# Sheet_1.net
KiCad netlist of a schematic drawn in Altium Designer
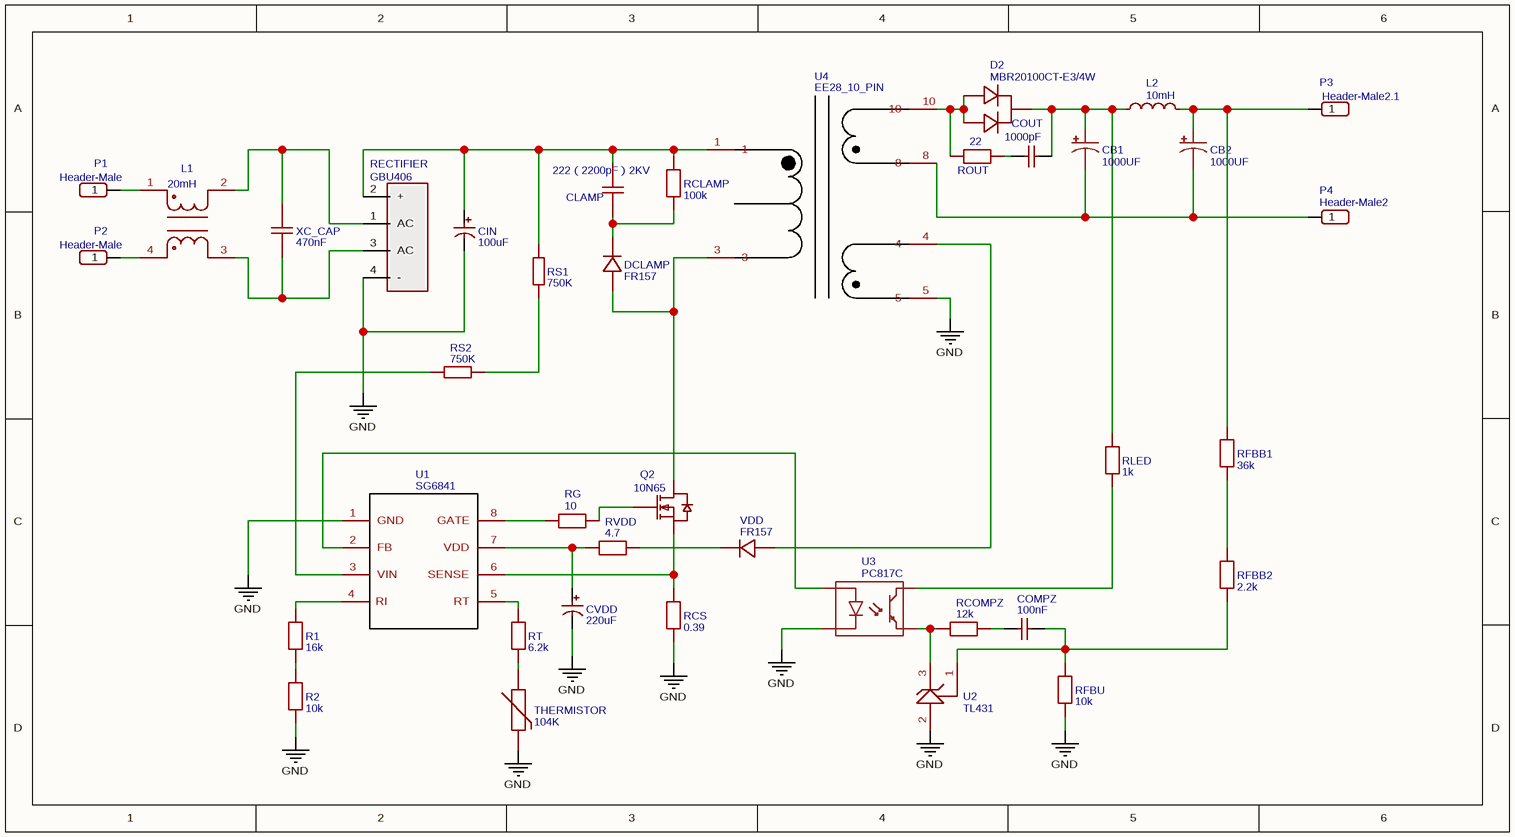
[diagram p0: Sheet_1.schdoc]

(export (version "E")
  (design (tool "Eeschema 10.0.6"))
  (components
    (comp (ref "CB1")
      (value "1000UF")
      (description "CAP-08070")
      (fields (field (name "CONTRIBUTOR") "SparkFun"))
      (libsource (lib "altium-import") (part "root_0_1000UF_"))
    )
    (comp (ref "CB2")
      (value "1000UF")
      (description "CAP-08070")
      (fields (field (name "CONTRIBUTOR") "SparkFun"))
      (libsource (lib "altium-import") (part "root_0_1000UF_"))
    )
    (comp (ref "CIN")
      (value "100uF")
      (fields
        (field (name "BOM_MANUFACTURER PART") "400V 100uF 18X30")
        (field (name "BOM_SUPPLIER PART") "C2767")
      )
      (libsource (lib "altium-import") (part "root_3_100uF_"))
    )
    (comp (ref "CLAMP")
      (value "222（2200pF）2KV")
      (fields (field (name "BOM_SUPPLIER PART") "C24926"))
      (libsource (lib "altium-import") (part "root_1_222（2200pF）2KV_"))
    )
    (comp (ref "COMPZ")
      (value "100nF")
      (fields
        (field (name "BOM_MANUFACTURER PART") "104/100V 20%")
        (field (name "BOM_SUPPLIER PART") "C26856")
      )
      (libsource (lib "altium-import") (part "root_0_100nF_"))
    )
    (comp (ref "COUT")
      (value "1000pF")
      (fields
        (field (name "BOM_MANUFACTURER PART") "102M 400V Y5V")
        (field (name "BOM_SUPPLIER PART") "C3704")
      )
      (libsource (lib "altium-import") (part "root_0_1000pF_"))
    )
    (comp (ref "CVDD")
      (value "220uF")
      (fields (field (name "BOM_MANUFACTURER PART") "220uf/35V") (field (name "BOM_SUPPLIER PART") "C2063"))
      (libsource (lib "altium-import") (part "root_3_220uF_"))
    )
    (comp (ref "D2")
      (value "MBR20100CT-E3/4W")
      (fields (field (name "BOM_SUPPLIER PART") "C222466") (field (name "CONTRIBUTOR") "LCSC"))
      (libsource (lib "altium-import") (part "root_3_MBR20100CT-E3/4W_"))
    )
    (comp (ref "DCLAMP")
      (value "FR157")
      (fields (field (name "BOM_SUPPLIER PART") "C2467"))
      (libsource (lib "altium-import") (part "root_1_FR157_"))
    )
    (comp (ref "L1")
      (value "20mH")
      (fields
        (field (name "BOM_SUPPLIER PART") "C148474")
        (field (name "BOM_MANUFACTURER PART") "UU9.8-10mH")
        (field (name "CONTRIBUTOR") "LCSC")
      )
      (libsource (lib "altium-import") (part "root_0_20mH_"))
    )
    (comp (ref "L2")
      (value "10mH")
      (fields
        (field (name "BOM_MANUFACTURER PART") "VLU0608-103K")
        (field (name "BOM_SUPPLIER PART") "C72613")
      )
      (libsource (lib "altium-import") (part "root_0_10mH_"))
    )
    (comp (ref "P1")
      (value "Header-Male")
      (fields
        (field (name "BOM_MANUFACTURER PART") "Header-Male-2.54_1x1")
        (field (name "BOM_SUPPLIER PART") "C81276")
      )
      (libsource (lib "altium-import") (part "root_2_Header-Male_"))
    )
    (comp (ref "P2")
      (value "Header-Male")
      (fields
        (field (name "BOM_MANUFACTURER PART") "Header-Male-2.54_1x1")
        (field (name "BOM_SUPPLIER PART") "C81276")
      )
      (libsource (lib "altium-import") (part "root_2_Header-Male_"))
    )
    (comp (ref "P3")
      (value "Header-Male2.1")
      (fields
        (field (name "BOM_MANUFACTURER PART") "Header-Male-2.54_1x1")
        (field (name "BOM_SUPPLIER PART") "C81276")
      )
      (libsource (lib "altium-import") (part "root_0_Header-Male2.1_"))
    )
    (comp (ref "P4")
      (value "Header-Male2")
      (fields
        (field (name "BOM_MANUFACTURER PART") "Header-Male-2.54_1x1")
        (field (name "BOM_SUPPLIER PART") "C81276")
      )
      (libsource (lib "altium-import") (part "root_0_Header-Male2_"))
    )
    (comp (ref "Q2")
      (value "10N65")
      (fields
        (field (name "BOM_MANUFACTURER PART") "10N65KL-TF3-T")
        (field (name "BOM_SUPPLIER PART") "C74166")
      )
      (libsource (lib "altium-import") (part "root_0_10N65_"))
    )
    (comp (ref "R1") (value "16k") (libsource (lib "altium-import") (part "root_1_16k_")))
    (comp (ref "R2") (value "10k") (libsource (lib "altium-import") (part "root_1_10k_")))
    (comp (ref "RCLAMP") (value "100k") (libsource (lib "altium-import") (part "root_1_100k_")))
    (comp (ref "RCOMPZ") (value "12k") (libsource (lib "altium-import") (part "root_0_12k_")))
    (comp (ref "RCS") (value "0.39") (libsource (lib "altium-import") (part "root_1_0.39_")))
    (comp (ref "RECTIFIER")
      (value "GBU406")
      (fields
        (field (name "BOM_MANUFACTURER PART") "GBU406 Rectifier bridge")
        (field (name "BOM_SUPPLIER PART") "C13432")
      )
      (libsource (lib "altium-import") (part "root_3_GBU406_"))
    )
    (comp (ref "RFBB1") (value "36k") (libsource (lib "altium-import") (part "root_1_36k_")))
    (comp (ref "RFBB2") (value "2.2k") (libsource (lib "altium-import") (part "root_1_2.2k_")))
    (comp (ref "RFBU") (value "10k") (libsource (lib "altium-import") (part "root_1_10k_")))
    (comp (ref "RG") (value "10") (libsource (lib "altium-import") (part "root_0_10_")))
    (comp (ref "RLED") (value "1k") (libsource (lib "altium-import") (part "root_1_1k_")))
    (comp (ref "ROUT") (value "22") (libsource (lib "altium-import") (part "root_0_22_")))
    (comp (ref "RS1")
      (value "750K")
      (fields (field (name "BOM_SUPPLIER PART") "C119386") (field (name "CONTRIBUTOR") "LCSC"))
      (libsource (lib "altium-import") (part "root_1_750K_"))
    )
    (comp (ref "RS2")
      (value "750K")
      (fields (field (name "BOM_SUPPLIER PART") "C119386") (field (name "CONTRIBUTOR") "LCSC"))
      (libsource (lib "altium-import") (part "root_0_750K_"))
    )
    (comp (ref "RT") (value "6.2k") (libsource (lib "altium-import") (part "root_1_6.2k_")))
    (comp (ref "RVDD") (value "4.7") (libsource (lib "altium-import") (part "root_0_4.7_")))
    (comp (ref "THERMISTOR")
      (value "104K")
      (fields (field (name "BOM_MANUFACTURER PART") "MF11-104K") (field (name "BOM_SUPPLIER PART") "C40773"))
      (libsource (lib "altium-import") (part "root_1_104K_"))
    )
    (comp (ref "U1")
      (value "SG6841")
      (fields (field (name "CONTRIBUTOR") "OpvS0OU3iRgTi1deEJgjG"))
      (libsource (lib "altium-import") (part "root_0_SG6841_"))
    )
    (comp (ref "U2")
      (value "TL431")
      (fields
        (field (name "BOM_MANUFACTURER PART") "TL431AILP")
        (field (name "BOM_SUPPLIER PART") "C72108")
        (field (name "CONTRIBUTOR") "LCSC")
      )
      (libsource (lib "altium-import") (part "root_1_TL431_"))
    )
    (comp (ref "U3") (value "PC817C") (libsource (lib "altium-import") (part "root_0_PC817C_")))
    (comp (ref "U4")
      (value "EE28_10_PIN")
      (fields (field (name "BOM_SUPPLIER PART") "undefined") (field (name "CONTRIBUTOR") "kevwe"))
      (libsource (lib "altium-import") (part "root_0_EE28_10_PIN_"))
    )
    (comp (ref "VDD")
      (value "FR157")
      (fields (field (name "BOM_SUPPLIER PART") "C2467"))
      (libsource (lib "altium-import") (part "root_2_FR157_"))
    )
    (comp (ref "XC_CAP")
      (value "470nF")
      (fields (field (name "BOM_SUPPLIER PART") "C281974") (field (name "CONTRIBUTOR") "LCSC"))
      (libsource (lib "altium-import") (part "root_0_470nF_"))
    )
  )
  (nets
    (net (code "1") (name "GND") (class "Default")
      (node (ref "CIN") (pin "2") (pinfunction "2_2") (pintype "passive"))
      (node (ref "CVDD") (pin "2") (pinfunction "2_2") (pintype "passive"))
      (node (ref "R2") (pin "1") (pinfunction "1_1") (pintype "passive"))
      (node (ref "RCS") (pin "1") (pinfunction "1_1") (pintype "passive"))
      (node (ref "RECTIFIER") (pin "4") (pinfunction "-_4") (pintype "passive"))
      (node (ref "RFBU") (pin "1") (pinfunction "1_1") (pintype "passive"))
      (node (ref "THERMISTOR") (pin "1") (pinfunction "1_1") (pintype "passive"))
      (node (ref "U1") (pin "1") (pinfunction "GND_1") (pintype "passive"))
      (node (ref "U2") (pin "2") (pinfunction "ANODE_2") (pintype "passive"))
      (node (ref "U3") (pin "2") (pinfunction "K_2") (pintype "passive"))
      (node (ref "U4") (pin "5") (pinfunction "5_5") (pintype "passive"))
    )
    (net (code "2") (name "Net-(CB1-Pad+)") (class "Default")
      (node (ref "CB1") (pin "+") (pinfunction "+_+") (pintype "passive"))
      (node (ref "COUT") (pin "2") (pinfunction "2_2") (pintype "passive"))
      (node (ref "D2") (pin "2") (pinfunction "2_2") (pintype "passive"))
      (node (ref "L2") (pin "1") (pinfunction "1_1") (pintype "passive"))
      (node (ref "RLED") (pin "2") (pinfunction "2_2") (pintype "passive"))
    )
    (net (code "3") (name "Net-(CB1-Pad-)") (class "Default")
      (node (ref "CB1") (pin "-") (pinfunction "-_-") (pintype "passive"))
      (node (ref "CB2") (pin "-") (pinfunction "-_-") (pintype "passive"))
      (node (ref "P4") (pin "1") (pinfunction "1_1") (pintype "passive"))
      (node (ref "U4") (pin "8") (pinfunction "8_8") (pintype "passive"))
    )
    (net (code "4") (name "Net-(CB2-Pad+)") (class "Default")
      (node (ref "CB2") (pin "+") (pinfunction "+_+") (pintype "passive"))
      (node (ref "L2") (pin "2") (pinfunction "2_2") (pintype "passive"))
      (node (ref "P3") (pin "1") (pinfunction "1_1") (pintype "passive"))
      (node (ref "RFBB1") (pin "2") (pinfunction "2_2") (pintype "passive"))
    )
    (net (code "5") (name "Net-(COMPZ-Pad1)") (class "Default")
      (node (ref "COMPZ") (pin "1") (pinfunction "1_1") (pintype "passive"))
      (node (ref "RCOMPZ") (pin "2") (pinfunction "2_2") (pintype "passive"))
    )
    (net (code "6") (name "Net-(COUT-Pad1)") (class "Default")
      (node (ref "COUT") (pin "1") (pinfunction "1_1") (pintype "passive"))
      (node (ref "ROUT") (pin "2") (pinfunction "2_2") (pintype "passive"))
    )
    (net (code "7") (name "Net-(D2-Pad1)") (class "Default")
      (node (ref "D2") (pin "1") (pinfunction "1_1") (pintype "passive"))
      (node (ref "D2") (pin "3") (pinfunction "3_3") (pintype "passive"))
      (node (ref "ROUT") (pin "1") (pinfunction "1_1") (pintype "passive"))
      (node (ref "U4") (pin "10") (pinfunction "10_10") (pintype "passive"))
    )
    (net (code "8") (name "Net-(DCLAMP-A)") (class "Default")
      (node (ref "DCLAMP") (pin "1") (pinfunction "A_1") (pintype "passive"))
      (node (ref "Q2") (pin "2") (pinfunction "D_2") (pintype "passive"))
      (node (ref "U4") (pin "3") (pinfunction "3_3") (pintype "passive"))
    )
    (net (code "9") (name "Net-(DCLAMP-K)") (class "Default")
      (node (ref "CLAMP") (pin "1") (pinfunction "1_1") (pintype "passive"))
      (node (ref "DCLAMP") (pin "2") (pinfunction "K_2") (pintype "passive"))
      (node (ref "RCLAMP") (pin "1") (pinfunction "1_1") (pintype "passive"))
    )
    (net (code "10") (name "Net-(L1-Pad1)") (class "Default")
      (node (ref "L1") (pin "1") (pinfunction "1_1") (pintype "passive"))
      (node (ref "P1") (pin "1") (pinfunction "1_1") (pintype "passive"))
    )
    (net (code "11") (name "Net-(L1-Pad2)") (class "Default")
      (node (ref "L1") (pin "2") (pinfunction "2_2") (pintype "passive"))
      (node (ref "RECTIFIER") (pin "1") (pinfunction "AC_1") (pintype "passive"))
      (node (ref "XC_CAP") (pin "1") (pinfunction "1_1") (pintype "passive"))
    )
    (net (code "12") (name "Net-(L1-Pad3)") (class "Default")
      (node (ref "L1") (pin "3") (pinfunction "3_3") (pintype "passive"))
      (node (ref "RECTIFIER") (pin "3") (pinfunction "AC_3") (pintype "passive"))
      (node (ref "XC_CAP") (pin "2") (pinfunction "2_2") (pintype "passive"))
    )
    (net (code "13") (name "Net-(L1-Pad4)") (class "Default")
      (node (ref "L1") (pin "4") (pinfunction "4_4") (pintype "passive"))
      (node (ref "P2") (pin "1") (pinfunction "1_1") (pintype "passive"))
    )
    (net (code "14") (name "Net-(Q2-G)") (class "Default")
      (node (ref "Q2") (pin "1") (pinfunction "G_1") (pintype "passive"))
      (node (ref "RG") (pin "2") (pinfunction "2_2") (pintype "passive"))
    )
    (net (code "15") (name "Net-(Q2-S)") (class "Default")
      (node (ref "Q2") (pin "3") (pinfunction "S_3") (pintype "passive"))
      (node (ref "RCS") (pin "2") (pinfunction "2_2") (pintype "passive"))
      (node (ref "U1") (pin "6") (pinfunction "SENSE_6") (pintype "passive"))
    )
    (net (code "16") (name "Net-(R1-Pad1)") (class "Default")
      (node (ref "R1") (pin "1") (pinfunction "1_1") (pintype "passive"))
      (node (ref "R2") (pin "2") (pinfunction "2_2") (pintype "passive"))
    )
    (net (code "17") (name "Net-(RECTIFIER-+)") (class "Default")
      (node (ref "CIN") (pin "1") (pinfunction "1_1") (pintype "passive"))
      (node (ref "CLAMP") (pin "2") (pinfunction "2_2") (pintype "passive"))
      (node (ref "RCLAMP") (pin "2") (pinfunction "2_2") (pintype "passive"))
      (node (ref "RECTIFIER") (pin "2") (pinfunction "+_2") (pintype "passive"))
      (node (ref "RS1") (pin "2") (pinfunction "2_2") (pintype "passive"))
      (node (ref "U4") (pin "1") (pinfunction "1_1") (pintype "passive"))
    )
    (net (code "18") (name "Net-(RFBB1-Pad1)") (class "Default")
      (node (ref "RFBB1") (pin "1") (pinfunction "1_1") (pintype "passive"))
      (node (ref "RFBB2") (pin "2") (pinfunction "2_2") (pintype "passive"))
    )
    (net (code "19") (name "Net-(RS1-Pad1)") (class "Default")
      (node (ref "RS1") (pin "1") (pinfunction "1_1") (pintype "passive"))
      (node (ref "RS2") (pin "2") (pinfunction "2_2") (pintype "passive"))
    )
    (net (code "20") (name "Net-(RT-Pad1)") (class "Default")
      (node (ref "RT") (pin "1") (pinfunction "1_1") (pintype "passive"))
      (node (ref "THERMISTOR") (pin "2") (pinfunction "2_2") (pintype "passive"))
    )
    (net (code "21") (name "Net-(U1-FB)") (class "Default")
      (node (ref "U1") (pin "2") (pinfunction "FB_2") (pintype "passive"))
      (node (ref "U3") (pin "1") (pinfunction "A_1") (pintype "passive"))
    )
    (net (code "22") (name "Net-(U1-GATE)") (class "Default")
      (node (ref "RG") (pin "1") (pinfunction "1_1") (pintype "passive"))
      (node (ref "U1") (pin "8") (pinfunction "GATE_8") (pintype "passive"))
    )
    (net (code "23") (name "Net-(U1-RI)") (class "Default")
      (node (ref "R1") (pin "2") (pinfunction "2_2") (pintype "passive"))
      (node (ref "U1") (pin "4") (pinfunction "RI_4") (pintype "passive"))
    )
    (net (code "24") (name "Net-(U1-RT)") (class "Default")
      (node (ref "RT") (pin "2") (pinfunction "2_2") (pintype "passive"))
      (node (ref "U1") (pin "5") (pinfunction "RT_5") (pintype "passive"))
    )
    (net (code "25") (name "Net-(U1-VDD)") (class "Default")
      (node (ref "CVDD") (pin "1") (pinfunction "1_1") (pintype "passive"))
      (node (ref "RVDD") (pin "1") (pinfunction "1_1") (pintype "passive"))
      (node (ref "U1") (pin "7") (pinfunction "VDD_7") (pintype "passive"))
    )
    (net (code "26") (name "Net-(U1-VIN)") (class "Default")
      (node (ref "RS2") (pin "1") (pinfunction "1_1") (pintype "passive"))
      (node (ref "U1") (pin "3") (pinfunction "VIN_3") (pintype "passive"))
    )
    (net (code "27") (name "Net-(U2-CATHODE)") (class "Default")
      (node (ref "RCOMPZ") (pin "1") (pinfunction "1_1") (pintype "passive"))
      (node (ref "U2") (pin "3") (pinfunction "CATHODE_3") (pintype "passive"))
      (node (ref "U3") (pin "3") (pinfunction "E_3") (pintype "passive"))
    )
    (net (code "28") (name "Net-(U2-REF)") (class "Default")
      (node (ref "COMPZ") (pin "2") (pinfunction "2_2") (pintype "passive"))
      (node (ref "RFBB2") (pin "1") (pinfunction "1_1") (pintype "passive"))
      (node (ref "RFBU") (pin "2") (pinfunction "2_2") (pintype "passive"))
      (node (ref "U2") (pin "1") (pinfunction "REF_1") (pintype "passive"))
    )
    (net (code "29") (name "Net-(U3-C)") (class "Default")
      (node (ref "RLED") (pin "1") (pinfunction "1_1") (pintype "passive"))
      (node (ref "U3") (pin "4") (pinfunction "C_4") (pintype "passive"))
    )
    (net (code "30") (name "Net-(VDD-A)") (class "Default")
      (node (ref "U4") (pin "4") (pinfunction "4_4") (pintype "passive"))
      (node (ref "VDD") (pin "1") (pinfunction "A_1") (pintype "passive"))
    )
    (net (code "31") (name "Net-(VDD-K)") (class "Default")
      (node (ref "RVDD") (pin "2") (pinfunction "2_2") (pintype "passive"))
      (node (ref "VDD") (pin "2") (pinfunction "K_2") (pintype "passive"))
    )
  )
)
